# LPEDT_revA1_bikeit_MCU_POWER_RESET.net
KiCad netlist of a schematic drawn in Altium Designer
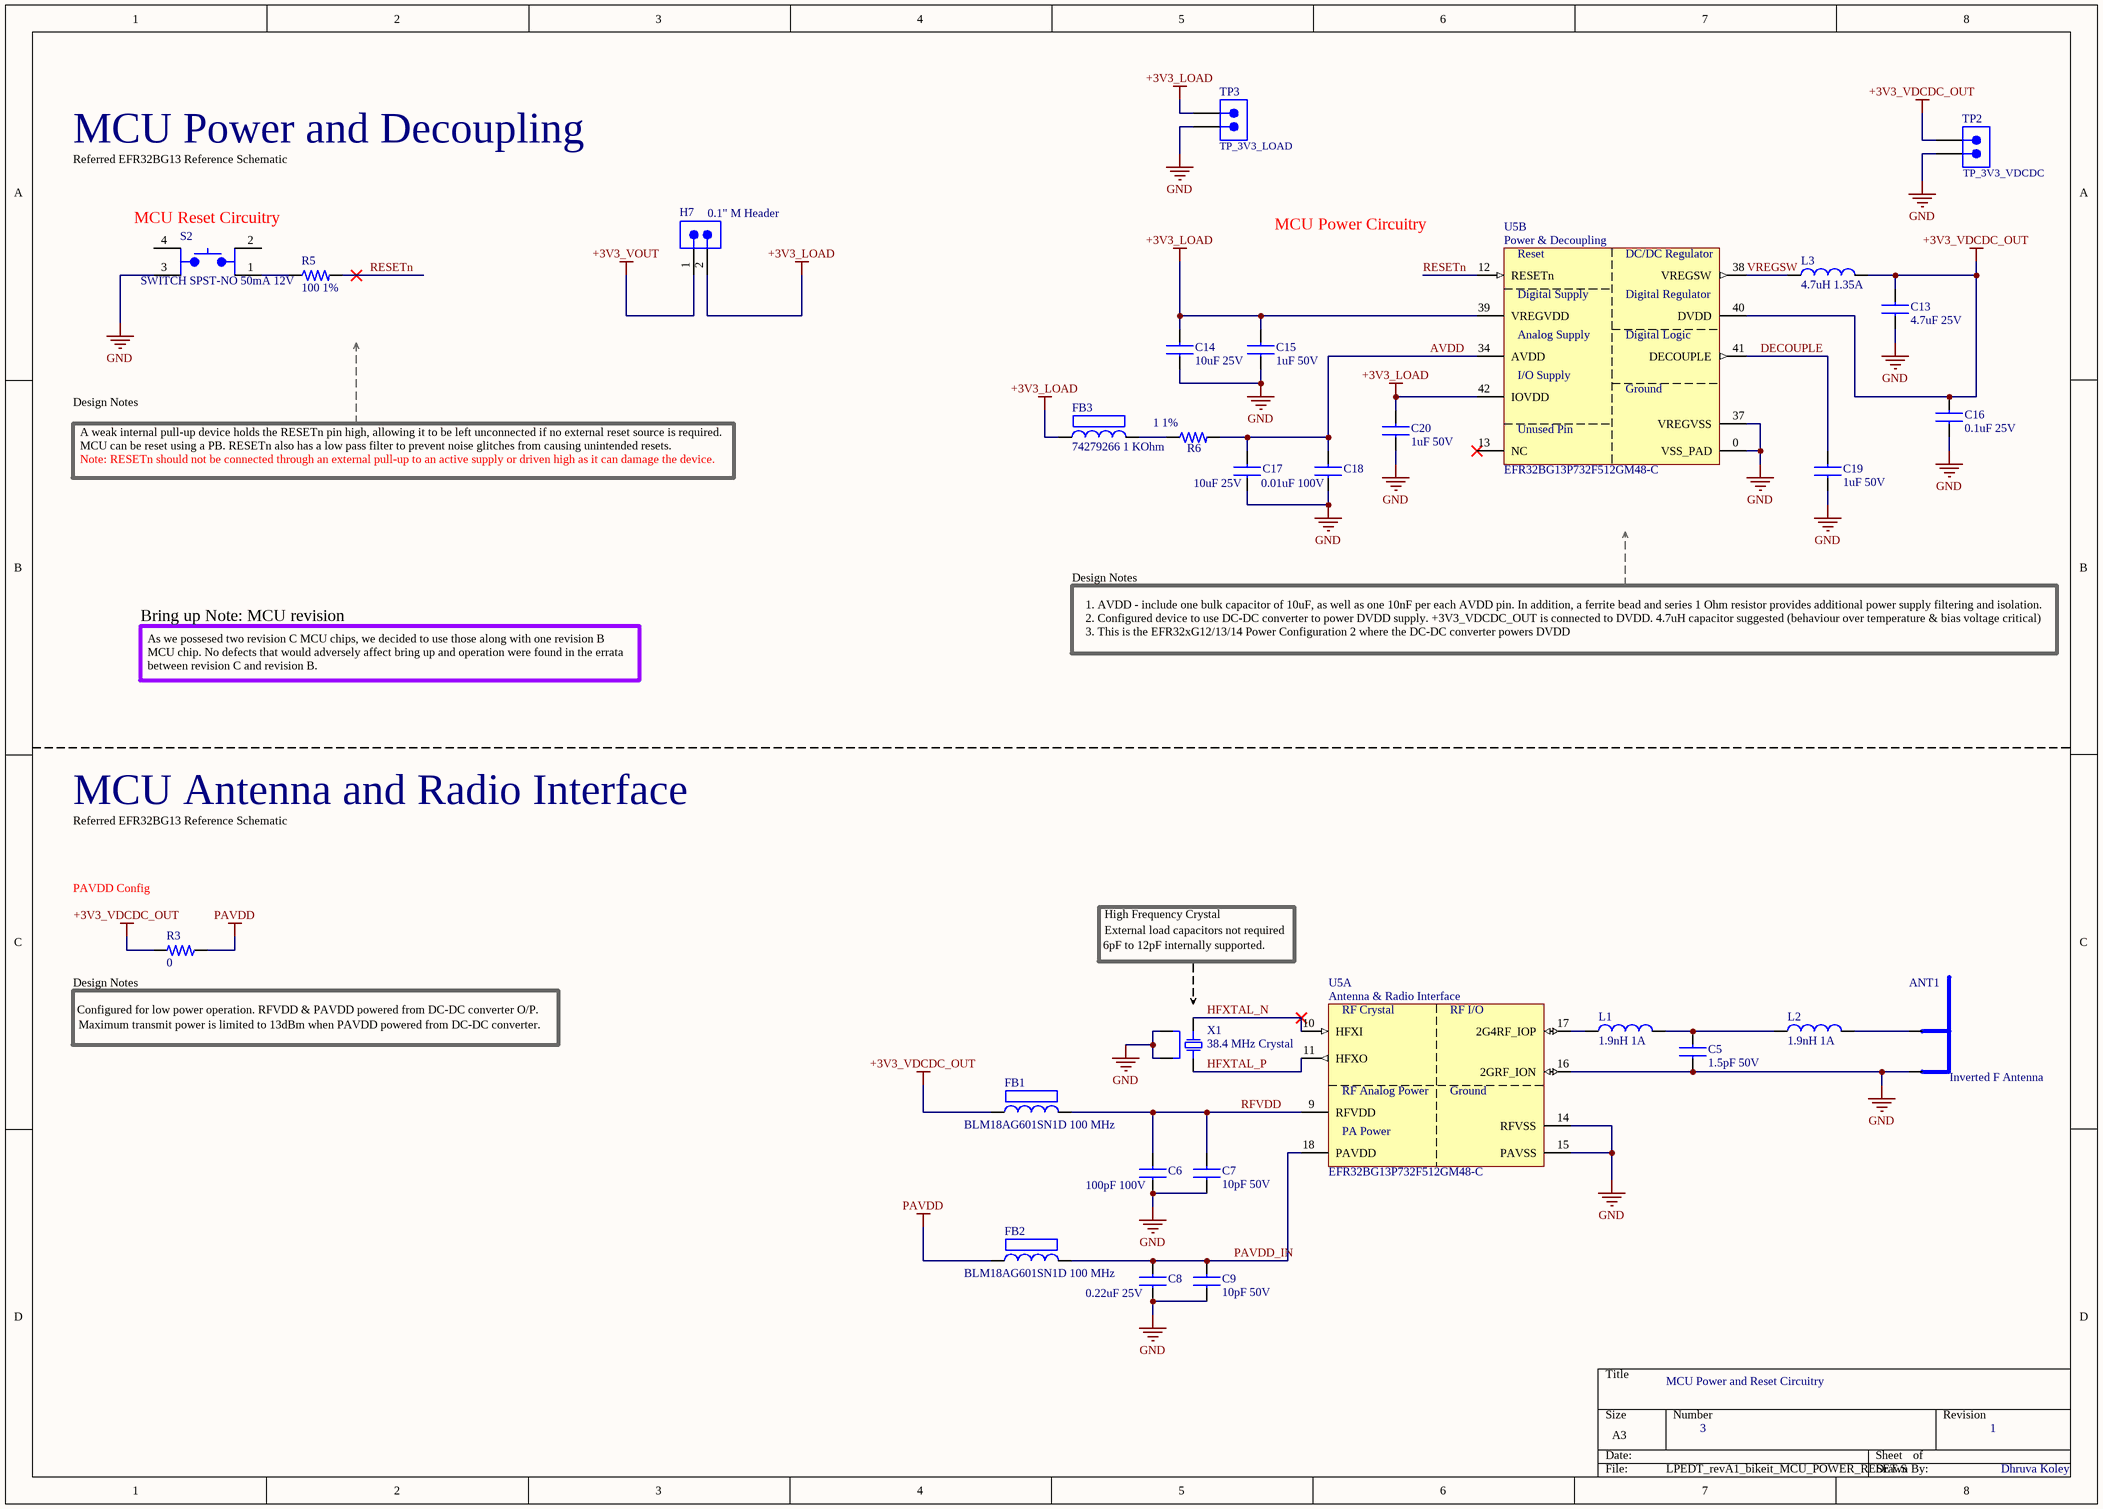
[diagram p0: LPEDT_revA1_bikeit_MCU_POWER_RESET.SchDoc]

(export (version "E")
  (design (tool "Eeschema 10.0.6"))
  (components
    (comp (ref "ANT1")
      (value "Inverted F Antenna")
      (footprint "MIFA")
      (description "Inverted F antenna for BT")
      (libsource (lib "LPEDT_revA1_bikeit_IL") (part "Inverted F Antenna"))
    )
    (comp (ref "C5")
      (value "1.5pF 50V")
      (footprint "CAP_0403_1.00mm*0.50mm")
      (description "1.5pF ±0.1pF 50V Ceramic Capacitor C0G, NP0 0402 (1005 Metric)")
      (fields
        (field (name "MANUFACTURER") "Johanson Technology Inc.")
        (field (name "MANUFACTURER PART NUMBER") "500R07S1R5BV4T")
      )
      (libsource (lib "LPEDT_revA1_bikeit_IL") (part "500R07S1R5BV4T"))
    )
    (comp (ref "C6")
      (value "100pF 100V")
      (footprint "CAP_0603_1.60mm*0.80mm")
      (description "Multilayer Ceramic Capacitors MLCC - SMD/SMT 100pF 100Volts C0G 0.01")
      (fields
        (field (name "MANUFACTURER") "Murata")
        (field (name "MANUFACTURER PART NUMBER") "GRM1885C2A101FA01D")
      )
      (libsource (lib "LPEDT_revA1_bikeit_IL") (part "GRM1885C2A101FA01D"))
    )
    (comp (ref "C7")
      (value "10pF 50V")
      (footprint "CAP_0603_1.60mm*0.80mm")
      (description "Cap Ceramic 10pF 50V C0G 1% SMD 0603 125C T/R")
      (fields
        (field (name "MANUFACTURER") "Murata")
        (field (name "MANUFACTURER PART NUMBER") "GRM1885C1H100FA01D")
      )
      (libsource (lib "LPEDT_revA1_bikeit_IL") (part "GRM1885C1H100FA01D"))
    )
    (comp (ref "C8")
      (value "0.22uF 25V")
      (footprint "CAP_0603_1.60mm*0.80mm")
      (description "Capacitor 220 nF 25 VDC PU=4000 ST, GRM188R71E224KA88D, Murata")
      (fields
        (field (name "MANUFACTURER") "Murata")
        (field (name "MANUFACTURER PART NUMBER") "GRM188R71E224KA88D")
      )
      (libsource (lib "LPEDT_revA1_bikeit_IL") (part "GRM188R71E224KA88D"))
    )
    (comp (ref "C9")
      (value "10pF 50V")
      (footprint "CAP_0603_1.60mm*0.80mm")
      (description "Cap Ceramic 10pF 50V C0G 1% SMD 0603 125C T/R")
      (fields
        (field (name "MANUFACTURER") "Murata")
        (field (name "MANUFACTURER PART NUMBER") "GRM1885C1H100FA01D")
      )
      (libsource (lib "LPEDT_revA1_bikeit_IL") (part "GRM1885C1H100FA01D"))
    )
    (comp (ref "C13")
      (value "4.7uF 25V")
      (footprint "CAP_0603_1.60mm*0.80mm")
      (description "Cap Ceramic 0603 4.7 uF 25 V ±10 % Tolerance X5R SMT Multilayer Ceramic Capacitor")
      (fields
        (field (name "MANUFACTURER") "Murata")
        (field (name "MANUFACTURER PART NUMBER") "GRM188R61E475KE11D")
      )
      (libsource (lib "LPEDT_revA1_bikeit_IL") (part "GRM188R61E475KE11D"))
    )
    (comp (ref "C14")
      (value "10uF 25V")
      (footprint "CAP_0805_2MM")
      (description "CAP CER 10UF 25V X5R 0805")
      (fields
        (field (name "MANUFACTURER") "Murata")
        (field (name "MANUFACTURER PART NUMBER") "GRM21BR61E106KA73K")
      )
      (libsource (lib "LPEDT_revA1_bikeit_IL") (part "GRM21BR61E106KA73K"))
    )
    (comp (ref "C15")
      (value "1uF 50V")
      (footprint "CAP_0603_1.60mm*0.80mm")
      (description "CAP, MLCC, AEC-Q200, X5R, 1uF, 50V, 0603")
      (fields
        (field (name "MANUFACTURER") "Murata")
        (field (name "MANUFACTURER PART NUMBER") "GRT188R61H105KE13D")
      )
      (libsource (lib "LPEDT_revA1_bikeit_IL") (part "GRT188R61H105KE13D"))
    )
    (comp (ref "C16")
      (value "0.1uF 25V")
      (footprint "CAP_0603_1.60mm*0.80mm")
      (description "CAP CER 0.1UF 25V X7R 0603")
      (fields
        (field (name "MANUFACTURER") "Murata")
        (field (name "MANUFACTURER PART NUMBER") "GCJ188R71E104KA12D")
      )
      (libsource (lib "LPEDT_revA1_bikeit") (part "GCJ188R71E104KA12D"))
    )
    (comp (ref "C17")
      (value "10uF 25V")
      (footprint "CAP_0805_2MM")
      (description "CAP CER 10UF 25V X5R 0805")
      (fields
        (field (name "MANUFACTURER") "Murata")
        (field (name "MANUFACTURER PART NUMBER") "GRM21BR61E106KA73K")
      )
      (libsource (lib "LPEDT_revA1_bikeit_IL") (part "GRM21BR61E106KA73K"))
    )
    (comp (ref "C18")
      (value "0.01uF 100V")
      (footprint "CAP_0603_1.60mm*0.80mm")
      (description "Multilayer Ceramic Capacitor, AEC-Q200 GCM Series, 0.01 F, 10%, X7R, 100 V RoHS Compliant: Yes")
      (fields
        (field (name "MANUFACTURER") "Murata")
        (field (name "MANUFACTURER PART NUMBER") "GCM188R72A103KA37J")
      )
      (libsource (lib "LPEDT_revA1_bikeit") (part "GCM188R72A103KA37D"))
    )
    (comp (ref "C19")
      (value "1uF 50V")
      (footprint "CAP_0603_1.60mm*0.80mm")
      (description "CAP, MLCC, AEC-Q200, X5R, 1uF, 50V, 0603")
      (fields
        (field (name "MANUFACTURER") "Murata")
        (field (name "MANUFACTURER PART NUMBER") "GRT188R61H105KE13D")
      )
      (libsource (lib "LPEDT_revA1_bikeit_IL") (part "GRT188R61H105KE13D"))
    )
    (comp (ref "C20")
      (value "1uF 50V")
      (footprint "CAP_0603_1.60mm*0.80mm")
      (description "CAP, MLCC, AEC-Q200, X5R, 1uF, 50V, 0603")
      (fields
        (field (name "MANUFACTURER") "Murata")
        (field (name "MANUFACTURER PART NUMBER") "GRT188R61H105KE13D")
      )
      (libsource (lib "LPEDT_revA1_bikeit_IL") (part "GRT188R61H105KE13D"))
    )
    (comp (ref "FB1")
      (value "BLM18AG601SN1D 100 MHz")
      (footprint "FB_Chip2PinSM127P600-8N")
      (description "Ferrite Bead, 0603 / 1608, 600 ohm, 500 mA, Série BLM18A, 0.38 ohm, ± 25%")
      (fields
        (field (name "MANUFACTURER") "Murata")
        (field (name "MANUFACTURER PART NUMBER") "BLM18AG601SN1D")
      )
      (libsource (lib "LPEDT_revA1_bikeit_IL") (part "BLM18AG601SN1D"))
    )
    (comp (ref "FB2")
      (value "BLM18AG601SN1D 100 MHz")
      (footprint "FB_Chip2PinSM127P600-8N")
      (description "Ferrite Bead, 0603 / 1608, 600 ohm, 500 mA, Série BLM18A, 0.38 ohm, ± 25%")
      (fields
        (field (name "MANUFACTURER") "Murata")
        (field (name "MANUFACTURER PART NUMBER") "BLM18AG601SN1D")
      )
      (libsource (lib "LPEDT_revA1_bikeit_IL") (part "BLM18AG601SN1D"))
    )
    (comp (ref "FB3")
      (value "74279266 1 KOhm")
      (footprint "FB_0603_1.60mm*0.80mm")
      (description "Ferrite Bead, 0603 [1608 Metric], 1 kohm, 200 mA, WE-CBF Series, 0.6 ohm, ± 25%")
      (fields
        (field (name "MANUFACTURER") "Wurth Electronics")
        (field (name "MANUFACTURER PART NUMBER") "74279266")
      )
      (libsource (lib "LPEDT_revA1_bikeit_IL") (part "74279266"))
    )
    (comp (ref "H7")
      (value "0.1\" M Header")
      (footprint "2-PIN_MALE_HEADER_01-IN")
      (description "CONN HEADER VERT 2POS 2.54MM")
      (fields
        (field (name "MANUFACTURER") "Sullins")
        (field (name "MANUFACTURER PART NUMBER") "PRPC002SAAN-RC")
      )
      (libsource (lib "LPEDT_revA1_bikeit_IL") (part "PRPC002SAAN-RC"))
    )
    (comp (ref "L1")
      (value "1.9nH 1A")
      (footprint "IND_0402")
      (description "1.9nH Unshielded Multilayer Inductor 1A 50mOhm Max 0402 (1005 Metric)")
      (libsource (lib "LPEDT_revA1_bikeit_IL") (part "LQG15WZ1N9S02D"))
    )
    (comp (ref "L2")
      (value "1.9nH 1A")
      (footprint "IND_0402")
      (description "1.9nH Unshielded Multilayer Inductor 1A 50mOhm Max 0402 (1005 Metric)")
      (libsource (lib "LPEDT_revA1_bikeit_IL") (part "LQG15WZ1N9S02D"))
    )
    (comp (ref "L3")
      (value "4.7uH 1.35A")
      (footprint "IND_WE-TPC 2828")
      (description "Fixed Inductors WE-TPC 2828 4.7uH 1.35A .1Ohm")
      (fields
        (field (name "MANUFACTURER") "Wurth Electronics")
        (field (name "MANUFACTURER PART NUMBER") "744025004")
      )
      (libsource (lib "LPEDT_revA1_bikeit_IL") (part "744025004"))
    )
    (comp (ref "R3")
      (value "0")
      (footprint "RES_C1005X04N")
      (description "RES SMD 0 OHM JUMPER 1/16W 0402")
      (fields
        (field (name "MANUFACTURER") "Stackpole Electronics")
        (field (name "MANUFACTURER PART NUMBER") "RMCF0402ZT0R00")
      )
      (libsource (lib "LPEDT_revA1_bikeit_IL") (part "RMCF0402ZT0R00"))
    )
    (comp (ref "R5")
      (value "100 1%")
      (footprint "RES_0603_1608X06")
      (description "RES SMD 100 1%")
      (fields
        (field (name "MANUFACTURER") "Stackpole Electronics")
        (field (name "MANUFACTURER PART NUMBER") "RMCF0603FT100R")
      )
      (libsource (lib "LPEDT_revA1_bikeit_IL") (part "RMCF0603FT100R"))
    )
    (comp (ref "R6")
      (value "1 1%")
      (footprint "RES_0603_1608X06")
      (description "RES SMD 1 OHM 1% 1/10W 0603")
      (fields
        (field (name "MANUFACTURER") "Panasonic")
        (field (name "MANUFACTURER PART NUMBER") "ERJ-3RQF1R0V")
      )
      (libsource (lib "LPEDT_revA1_bikeit_IL") (part "ERJ-3RQF1R0V"))
    )
    (comp (ref "S2")
      (value "SWITCH SPST-NO 50mA 12V")
      (footprint "SW_TL3305AF260QG")
      (description "SWITCH TACTILE SPST-NO 50MA 12V")
      (fields
        (field (name "MANUFACTURER") "E-Switch")
        (field (name "MANUFACTURER PART NUMBER") "TL3305AF260QG")
      )
      (libsource (lib "LPEDT_revA1_bikeit_IL") (part "TL3305AF260QG"))
    )
    (comp (ref "TP2")
      (value "TP_3V3_VDCDC")
      (footprint "TP10x_Probe")
      (libsource (lib "LPEDT_revA1_bikeit_IL") (part "Test Point"))
    )
    (comp (ref "TP3")
      (value "TP_3V3_LOAD")
      (footprint "TP10x_Probe")
      (libsource (lib "LPEDT_revA1_bikeit_IL") (part "Test Point"))
    )
    (comp (ref "U5")
      (value "EFR32BG13P732F512GM48-C")
      (footprint "MCU_QFN50P700X700X90_HS-49N")
      (description "BLUE GECKO QFN48 2.4 GHZ 512KB 6")
      (fields (field (name "MANUFACTURER") "Silicon Labs"))
      (libsource (lib "LPEDT_revA1_bikeit_IL") (part "EFR32BG13P732F512GM48-C"))
    )
    (comp (ref "X1")
      (value "38.4 MHz Crystal")
      (footprint "SMD_4 CRYSTAL")
      (description "CRYSTAL 38.4000MHZ 8PF SMD")
      (fields
        (field (name "MANUFACTURER") "Kyocera AVX")
        (field (name "MANUFACTURER PART NUMBER") "CX2016DB38400D0FLJCC")
      )
      (libsource (lib "LPEDT_revA1_bikeit_IL") (part "CX2016DB38400D0FLJCC"))
    )
  )
  (nets
    (net (code "1") (name "+3V3_LOAD") (class "Default")
      (node (ref "C14") (pin "1") (pinfunction "1_1") (pintype "passive"))
      (node (ref "C15") (pin "1") (pinfunction "1_1") (pintype "passive"))
      (node (ref "C20") (pin "1") (pinfunction "1_1") (pintype "passive"))
      (node (ref "FB3") (pin "1") (pinfunction "1_1") (pintype "passive"))
      (node (ref "H7") (pin "2") (pinfunction "2_2") (pintype "passive"))
      (node (ref "TP3") (pin "1") (pinfunction "GND_1") (pintype "passive"))
      (node (ref "U5") (pin "39") (pinfunction "VREGVDD_39") (pintype "power_in"))
      (node (ref "U5") (pin "42") (pinfunction "IOVDD_42") (pintype "power_in"))
    )
    (net (code "2") (name "+3V3_VDCDC_OUT") (class "Default")
      (node (ref "C13") (pin "1") (pinfunction "1_1") (pintype "passive"))
      (node (ref "C16") (pin "1") (pinfunction "1_1") (pintype "passive"))
      (node (ref "FB1") (pin "1") (pinfunction "1_1") (pintype "passive"))
      (node (ref "L3") (pin "2") (pinfunction "2_2") (pintype "passive"))
      (node (ref "R3") (pin "2") (pinfunction "2_2") (pintype "passive"))
      (node (ref "TP2") (pin "1") (pinfunction "GND_1") (pintype "passive"))
      (node (ref "U5") (pin "40") (pinfunction "DVDD_40") (pintype "power_in"))
    )
    (net (code "3") (name "+3V3_VOUT") (class "Default")
      (node (ref "H7") (pin "1") (pinfunction "1_1") (pintype "passive"))
    )
    (net (code "4") (name "/AVDD") (class "Default")
      (node (ref "C17") (pin "1") (pinfunction "1_1") (pintype "passive"))
      (node (ref "C18") (pin "1") (pinfunction "1_1") (pintype "passive"))
      (node (ref "R6") (pin "2") (pinfunction "2_2") (pintype "passive"))
      (node (ref "U5") (pin "34") (pinfunction "AVDD_34") (pintype "power_in"))
    )
    (net (code "5") (name "/DECOUPLE") (class "Default")
      (node (ref "C19") (pin "1") (pinfunction "1_1") (pintype "passive"))
      (node (ref "U5") (pin "41") (pinfunction "DECOUPLE_41") (pintype "output"))
    )
    (net (code "6") (name "/HFXTAL_N") (class "Default")
      (node (ref "U5") (pin "10") (pinfunction "HFXI_10") (pintype "input"))
      (node (ref "X1") (pin "3") (pinfunction "HOT_3") (pintype "passive"))
    )
    (net (code "7") (name "/HFXTAL_P") (class "Default")
      (node (ref "U5") (pin "11") (pinfunction "HFXO_11") (pintype "output"))
      (node (ref "X1") (pin "1") (pinfunction "HOT_1") (pintype "passive"))
    )
    (net (code "8") (name "/PAVDD_IN") (class "Default")
      (node (ref "C8") (pin "1") (pinfunction "1_1") (pintype "passive"))
      (node (ref "C9") (pin "1") (pinfunction "1_1") (pintype "passive"))
      (node (ref "FB2") (pin "2") (pinfunction "2_2") (pintype "passive"))
      (node (ref "U5") (pin "18") (pinfunction "PAVDD_18") (pintype "power_in"))
    )
    (net (code "9") (name "/RESETn") (class "Default")
      (node (ref "R5") (pin "2") (pinfunction "2_2") (pintype "passive"))
      (node (ref "U5") (pin "12") (pinfunction "RESETn_12") (pintype "input"))
    )
    (net (code "10") (name "/RFVDD") (class "Default")
      (node (ref "C6") (pin "1") (pinfunction "1_1") (pintype "passive"))
      (node (ref "C7") (pin "1") (pinfunction "1_1") (pintype "passive"))
      (node (ref "FB1") (pin "2") (pinfunction "2_2") (pintype "passive"))
      (node (ref "U5") (pin "9") (pinfunction "RFVDD_9") (pintype "power_in"))
    )
    (net (code "11") (name "/VREGSW") (class "Default")
      (node (ref "L3") (pin "1") (pinfunction "1_1") (pintype "passive"))
      (node (ref "U5") (pin "38") (pinfunction "VREGSW_38") (pintype "output"))
    )
    (net (code "12") (name "GND") (class "Default")
      (node (ref "ANT1") (pin "GND") (pinfunction "GND_GND") (pintype "power_in"))
      (node (ref "C13") (pin "2") (pinfunction "2_2") (pintype "passive"))
      (node (ref "C14") (pin "2") (pinfunction "2_2") (pintype "passive"))
      (node (ref "C15") (pin "2") (pinfunction "2_2") (pintype "passive"))
      (node (ref "C16") (pin "2") (pinfunction "2_2") (pintype "passive"))
      (node (ref "C17") (pin "2") (pinfunction "2_2") (pintype "passive"))
      (node (ref "C18") (pin "2") (pinfunction "2_2") (pintype "passive"))
      (node (ref "C19") (pin "2") (pinfunction "2_2") (pintype "passive"))
      (node (ref "C20") (pin "2") (pinfunction "2_2") (pintype "passive"))
      (node (ref "C5") (pin "2") (pinfunction "2_2") (pintype "passive"))
      (node (ref "C6") (pin "2") (pinfunction "2_2") (pintype "passive"))
      (node (ref "C7") (pin "2") (pinfunction "2_2") (pintype "passive"))
      (node (ref "C8") (pin "2") (pinfunction "2_2") (pintype "passive"))
      (node (ref "C9") (pin "2") (pinfunction "2_2") (pintype "passive"))
      (node (ref "S2") (pin "3") (pinfunction "3_3") (pintype "passive"))
      (node (ref "TP2") (pin "2") (pinfunction "SIG_2") (pintype "passive"))
      (node (ref "TP3") (pin "2") (pinfunction "SIG_2") (pintype "passive"))
      (node (ref "U5") (pin "0") (pinfunction "VSS_PAD_0") (pintype "passive"))
      (node (ref "U5") (pin "14") (pinfunction "RFVSS_14") (pintype "power_in"))
      (node (ref "U5") (pin "15") (pinfunction "PAVSS_15") (pintype "power_in"))
      (node (ref "U5") (pin "16") (pinfunction "2GRF_ION_16") (pintype "bidirectional"))
      (node (ref "U5") (pin "37") (pinfunction "VREGVSS_37") (pintype "passive"))
      (node (ref "X1") (pin "2") (pinfunction "GND_2") (pintype "passive"))
      (node (ref "X1") (pin "4") (pinfunction "GND_4") (pintype "passive"))
    )
    (net (code "13") (name "Net-(ANT1-PadFEED)") (class "Default")
      (node (ref "ANT1") (pin "FEED") (pinfunction "FEED_FEED") (pintype "passive"))
      (node (ref "L2") (pin "2") (pinfunction "2_2") (pintype "passive"))
    )
    (net (code "14") (name "Net-(C5-Pad1)") (class "Default")
      (node (ref "C5") (pin "1") (pinfunction "1_1") (pintype "passive"))
      (node (ref "L1") (pin "2") (pinfunction "2_2") (pintype "passive"))
      (node (ref "L2") (pin "1") (pinfunction "1_1") (pintype "passive"))
    )
    (net (code "15") (name "Net-(FB3-Pad2)") (class "Default")
      (node (ref "FB3") (pin "2") (pinfunction "2_2") (pintype "passive"))
      (node (ref "R6") (pin "1") (pinfunction "1_1") (pintype "passive"))
    )
    (net (code "16") (name "Net-(R5-Pad1)") (class "Default")
      (node (ref "R5") (pin "1") (pinfunction "1_1") (pintype "passive"))
      (node (ref "S2") (pin "1") (pinfunction "1_1") (pintype "passive"))
    )
    (net (code "17") (name "Net-(U5A-2G4RF_IOP)") (class "Default")
      (node (ref "L1") (pin "1") (pinfunction "1_1") (pintype "passive"))
      (node (ref "U5") (pin "17") (pinfunction "2G4RF_IOP_17") (pintype "bidirectional"))
    )
    (net (code "18") (name "PAVDD") (class "Default")
      (node (ref "FB2") (pin "1") (pinfunction "1_1") (pintype "passive"))
      (node (ref "R3") (pin "1") (pinfunction "1_1") (pintype "passive"))
    )
    (net (code "19") (name "unconnected-(S2-Pad2)") (class "Default")
      (node (ref "S2") (pin "2") (pinfunction "2_2") (pintype "passive"))
    )
    (net (code "20") (name "unconnected-(S2-Pad4)") (class "Default")
      (node (ref "S2") (pin "4") (pinfunction "4_4") (pintype "passive"))
    )
    (net (code "21") (name "unconnected-(U5B-NC-Pad13)") (class "Default")
      (node (ref "U5") (pin "13") (pinfunction "NC_13") (pintype "passive+no_connect"))
    )
  )
)
